# cpu3_5e2.net
KiCad netlist of a schematic drawn in EAGLE
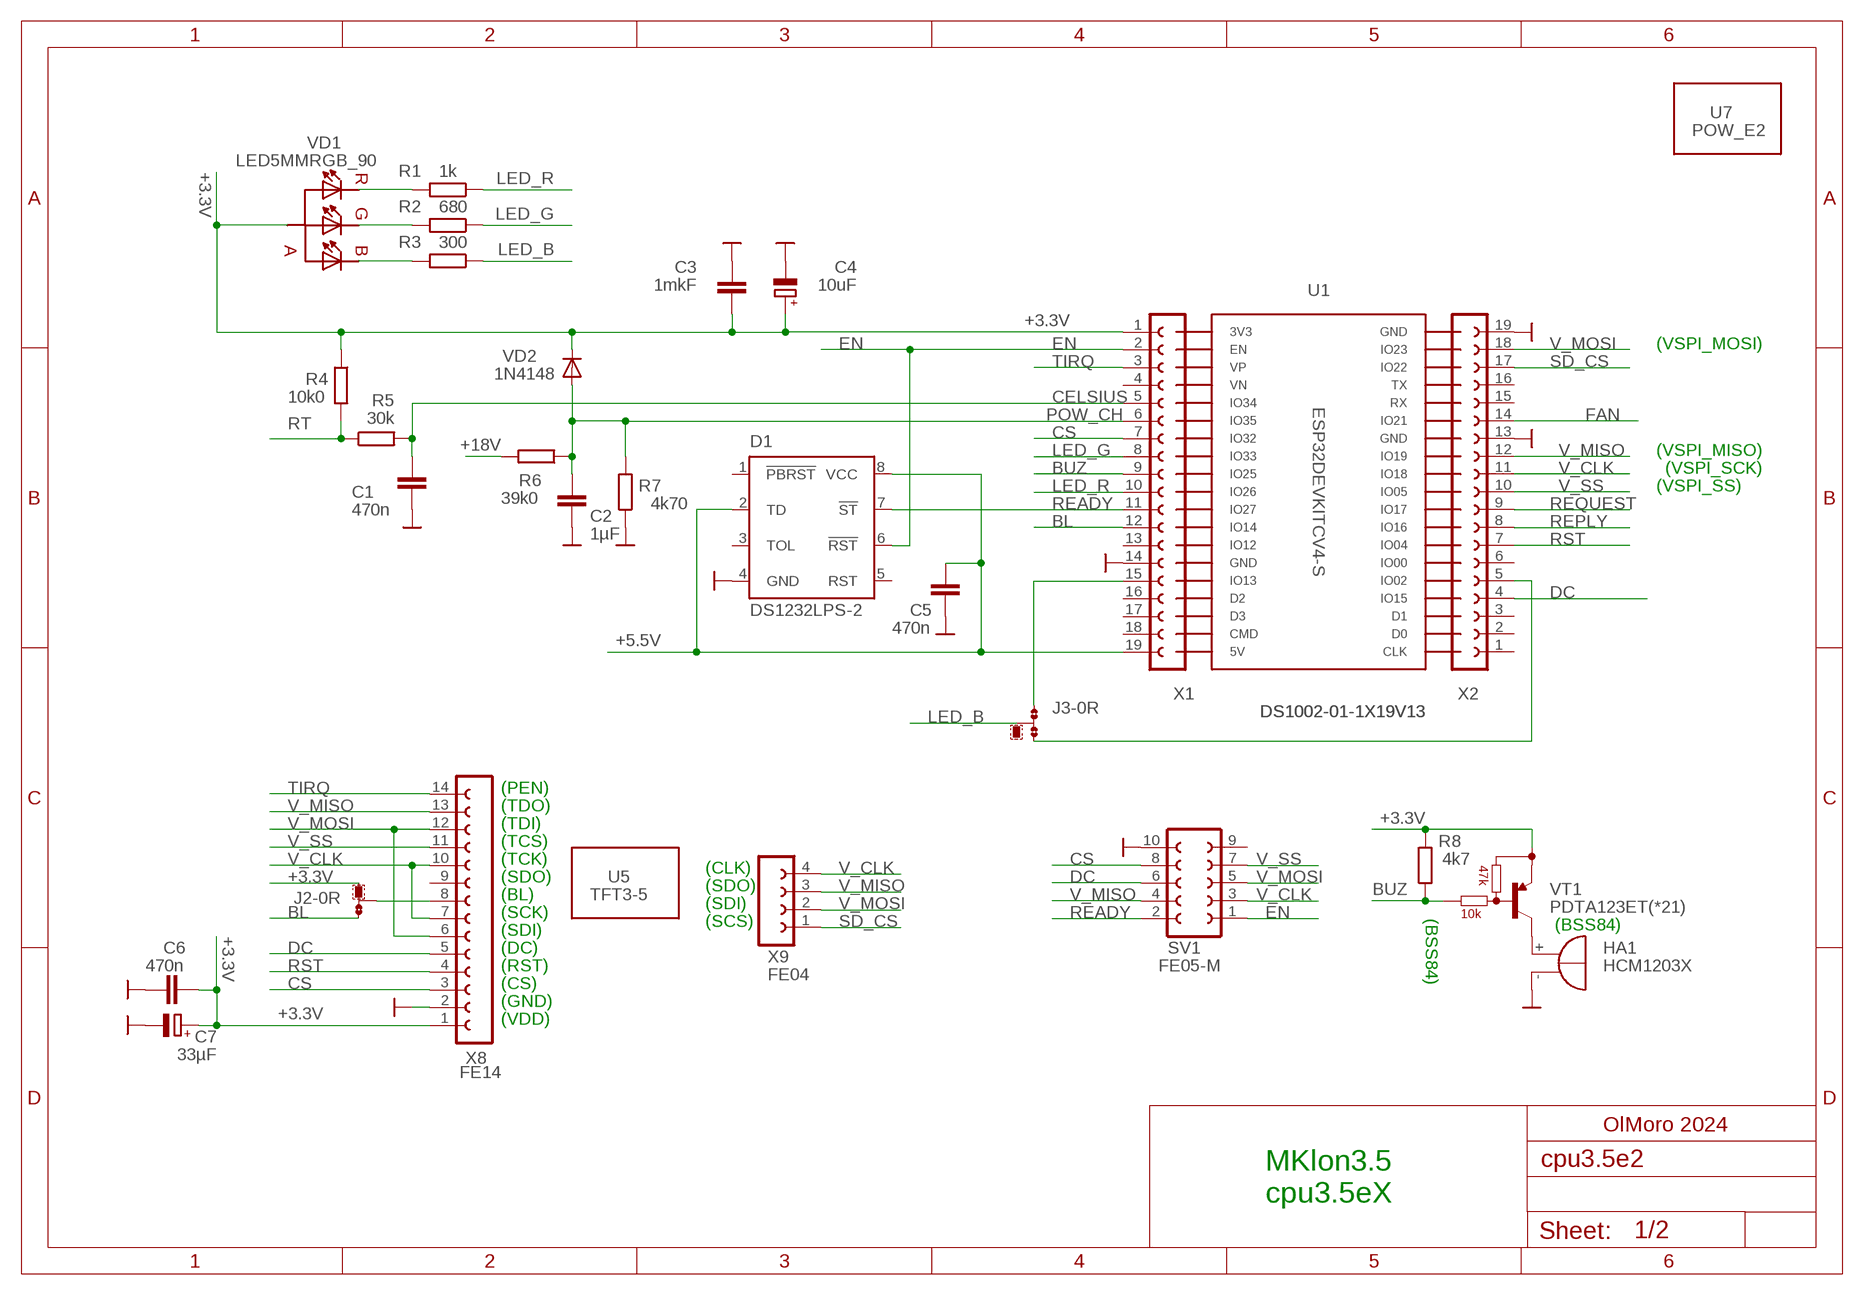
[diagram p0: schematic, sheet 1]
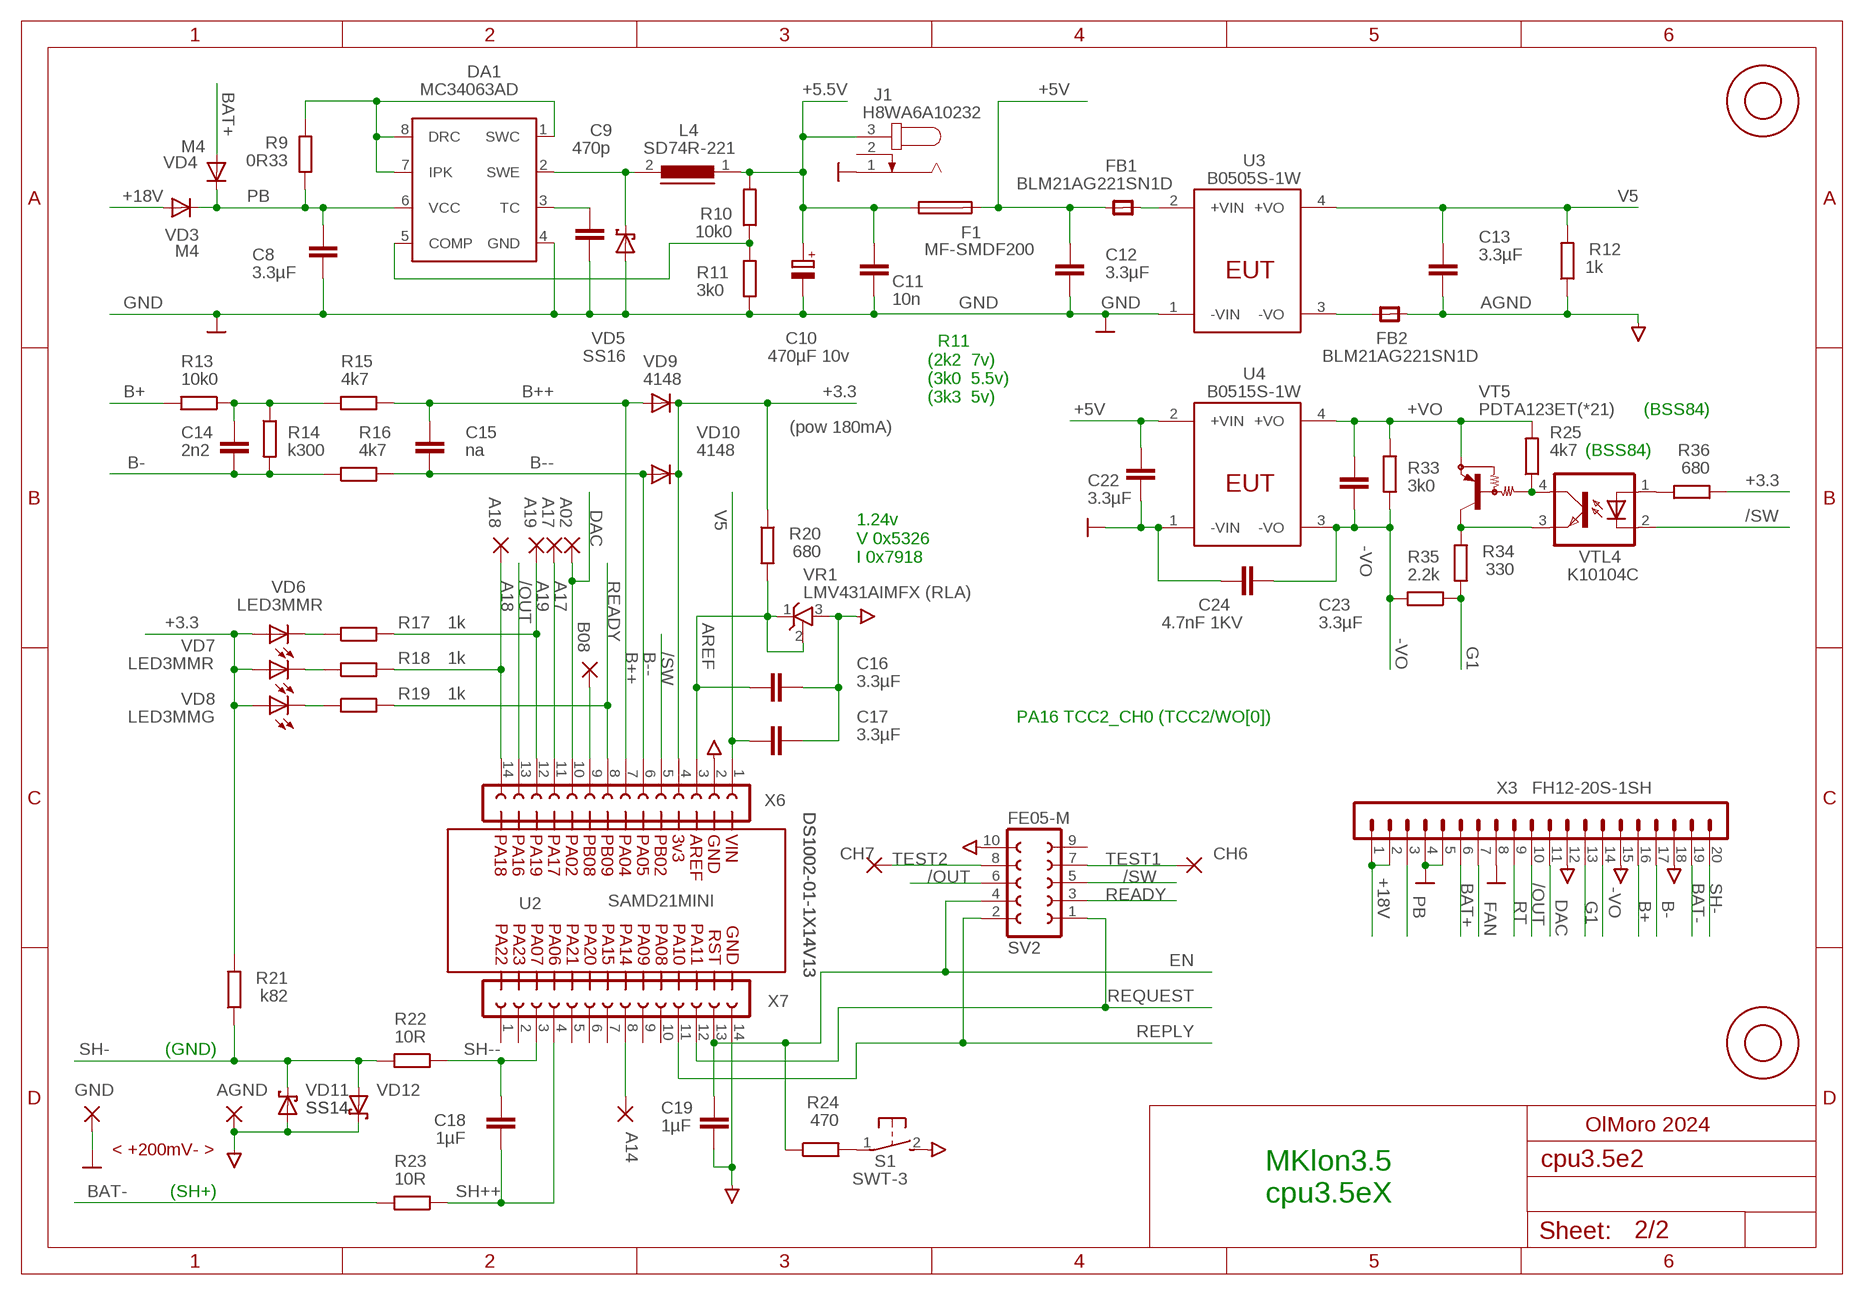
[diagram p1: schematic, sheet 2]

(export (version "E")
  (design (tool "Eeschema 10.0.6"))
  (components
    (comp (ref "A02")
      (value "WIREPAD1,6/0,8")
      (footprint "eagle-import:1,6_0,8")
      (libsource (lib "eagle-import") (part "WIREPAD1,6/0,8"))
    )
    (comp (ref "A14")
      (value "WIREPAD1,6/0,8")
      (footprint "eagle-import:1,6_0,8")
      (libsource (lib "eagle-import") (part "WIREPAD1,6/0,8"))
    )
    (comp (ref "A17")
      (value "WIREPAD1,6/0,8")
      (footprint "eagle-import:1,6_0,8")
      (libsource (lib "eagle-import") (part "WIREPAD1,6/0,8"))
    )
    (comp (ref "A18")
      (value "WIREPAD1,6/0,8")
      (footprint "eagle-import:1,6_0,8")
      (libsource (lib "eagle-import") (part "WIREPAD1,6/0,8"))
    )
    (comp (ref "A19")
      (value "WIREPAD1,6/0,8")
      (footprint "eagle-import:1,6_0,8")
      (libsource (lib "eagle-import") (part "WIREPAD1,6/0,8"))
    )
    (comp (ref "AGND")
      (value "AGND")
      (footprint "eagle-import:4,16O1,6")
      (libsource (lib "eagle-import") (part "WIREPAD4,16O1,6"))
    )
    (comp (ref "B08")
      (value "WIREPAD1,6/0,8")
      (footprint "eagle-import:1,6_0,8")
      (libsource (lib "eagle-import") (part "WIREPAD1,6/0,8"))
    )
    (comp (ref "C8")
      (value "3.3µF")
      (footprint "eagle-import:C0805")
      (libsource (lib "eagle-import") (part "C-EUC0805"))
    )
    (comp (ref "C9")
      (value "470p")
      (footprint "eagle-import:C0805")
      (libsource (lib "eagle-import") (part "C-EUC0805"))
    )
    (comp (ref "C10")
      (value "470µF 10v")
      (footprint "eagle-import:E5-8,5")
      (libsource (lib "eagle-import") (part "CPOL-EUE5-8.5"))
    )
    (comp (ref "C11")
      (value "10n")
      (footprint "eagle-import:C0805")
      (libsource (lib "eagle-import") (part "C-EUC0805"))
    )
    (comp (ref "C12")
      (value "3.3µF")
      (footprint "eagle-import:C0805")
      (libsource (lib "eagle-import") (part "C-EUC0805"))
    )
    (comp (ref "C13")
      (value "3.3µF")
      (footprint "eagle-import:C0805")
      (libsource (lib "eagle-import") (part "C-EUC0805"))
    )
    (comp (ref "C14")
      (value "2n2")
      (footprint "eagle-import:C0805")
      (libsource (lib "eagle-import") (part "C-EUC0805"))
    )
    (comp (ref "C15")
      (value "na")
      (footprint "eagle-import:C0805")
      (libsource (lib "eagle-import") (part "C-EUC0805"))
    )
    (comp (ref "C16")
      (value "3.3µF")
      (footprint "eagle-import:C0805")
      (libsource (lib "eagle-import") (part "C-EUC0805"))
    )
    (comp (ref "C17")
      (value "3.3µF")
      (footprint "eagle-import:C0805")
      (libsource (lib "eagle-import") (part "C-EUC0805"))
    )
    (comp (ref "C18")
      (value "1µF")
      (footprint "eagle-import:C0805")
      (libsource (lib "eagle-import") (part "C-EUC0805"))
    )
    (comp (ref "C19")
      (value "1µF")
      (footprint "eagle-import:C0805")
      (libsource (lib "eagle-import") (part "C-EUC0805"))
    )
    (comp (ref "C22")
      (value "3.3µF")
      (footprint "eagle-import:C0805")
      (libsource (lib "eagle-import") (part "C-EUC0805"))
    )
    (comp (ref "C23")
      (value "3.3µF")
      (footprint "eagle-import:C0805")
      (libsource (lib "eagle-import") (part "C-EUC0805"))
    )
    (comp (ref "C24")
      (value "4.7nF 1KV")
      (footprint "eagle-import:C050-024X044")
      (libsource (lib "eagle-import") (part "C-EU050-024X044"))
    )
    (comp (ref "CH6")
      (value "WIREPAD1,6/0,8")
      (footprint "eagle-import:1,6_0,8")
      (libsource (lib "eagle-import") (part "WIREPAD1,6/0,8"))
    )
    (comp (ref "CH7")
      (value "WIREPAD1,6/0,8")
      (footprint "eagle-import:1,6_0,8")
      (libsource (lib "eagle-import") (part "WIREPAD1,6/0,8"))
    )
    (comp (ref "DA1")
      (value "MC34063AD")
      (footprint "eagle-import:SO08")
      (libsource (lib "eagle-import") (part "MC34063AD"))
    )
    (comp (ref "F1")
      (value "MF-SMDF200")
      (footprint "eagle-import:MF-SMDF050")
      (libsource (lib "eagle-import") (part "MF-SMDF200"))
    )
    (comp (ref "FB1")
      (value "BLM21AG221SN1D")
      (footprint "eagle-import:0805")
      (libsource (lib "eagle-import") (part "FERRITE0805"))
    )
    (comp (ref "FB2")
      (value "BLM21AG221SN1D")
      (footprint "eagle-import:0805")
      (libsource (lib "eagle-import") (part "FERRITE0805"))
    )
    (comp (ref "GND")
      (value "GND")
      (footprint "eagle-import:4,16O1,6")
      (libsource (lib "eagle-import") (part "WIREPAD4,16O1,6"))
    )
    (comp (ref "J1")
      (value "H8WA6A10232")
      (footprint "eagle-import:SPC4077")
      (libsource (lib "eagle-import") (part "JACK-PLUG0"))
    )
    (comp (ref "L4")
      (value "SD74R-221")
      (footprint "eagle-import:DR74")
      (libsource (lib "eagle-import") (part "DR74"))
    )
    (comp (ref "R9")
      (value "0R33")
      (footprint "eagle-import:R0805")
      (libsource (lib "eagle-import") (part "R-EU_R0805"))
    )
    (comp (ref "R10")
      (value "10k0")
      (footprint "eagle-import:R0805")
      (libsource (lib "eagle-import") (part "R-EU_R0805"))
    )
    (comp (ref "R11")
      (value "3k0")
      (footprint "eagle-import:R0805")
      (libsource (lib "eagle-import") (part "R-EU_R0805"))
    )
    (comp (ref "R12")
      (value "1k")
      (footprint "eagle-import:R0805")
      (libsource (lib "eagle-import") (part "R-EU_R0805"))
    )
    (comp (ref "R13")
      (value "10k0")
      (footprint "eagle-import:R0805")
      (libsource (lib "eagle-import") (part "R-EU_R0805"))
    )
    (comp (ref "R14")
      (value "k300")
      (footprint "eagle-import:R0805")
      (libsource (lib "eagle-import") (part "R-EU_R0805"))
    )
    (comp (ref "R15")
      (value "4k7")
      (footprint "eagle-import:R0805")
      (libsource (lib "eagle-import") (part "R-EU_R0805"))
    )
    (comp (ref "R16")
      (value "4k7")
      (footprint "eagle-import:R0805")
      (libsource (lib "eagle-import") (part "R-EU_R0805"))
    )
    (comp (ref "R17")
      (value "1k")
      (footprint "eagle-import:R0805")
      (libsource (lib "eagle-import") (part "R-EU_R0805"))
    )
    (comp (ref "R18")
      (value "1k")
      (footprint "eagle-import:R0805")
      (libsource (lib "eagle-import") (part "R-EU_R0805"))
    )
    (comp (ref "R19")
      (value "1k")
      (footprint "eagle-import:R0805")
      (libsource (lib "eagle-import") (part "R-EU_R0805"))
    )
    (comp (ref "R20")
      (value "680")
      (footprint "eagle-import:R0805")
      (libsource (lib "eagle-import") (part "R-EU_R0805"))
    )
    (comp (ref "R21")
      (value "k82")
      (footprint "eagle-import:R0805")
      (libsource (lib "eagle-import") (part "R-EU_R0805"))
    )
    (comp (ref "R22")
      (value "10R")
      (footprint "eagle-import:R0805")
      (libsource (lib "eagle-import") (part "R-EU_R0805"))
    )
    (comp (ref "R23")
      (value "10R")
      (footprint "eagle-import:R0805")
      (libsource (lib "eagle-import") (part "R-EU_R0805"))
    )
    (comp (ref "R24")
      (value "470")
      (footprint "eagle-import:R0805")
      (libsource (lib "eagle-import") (part "R-EU_R0805"))
    )
    (comp (ref "R25")
      (value "4k7")
      (footprint "eagle-import:R0805")
      (libsource (lib "eagle-import") (part "R-EU_R0805"))
    )
    (comp (ref "R33")
      (value "3k0")
      (footprint "eagle-import:R0805")
      (libsource (lib "eagle-import") (part "R-EU_R0805"))
    )
    (comp (ref "R34")
      (value "330")
      (footprint "eagle-import:R0805")
      (libsource (lib "eagle-import") (part "R-EU_R0805"))
    )
    (comp (ref "R35")
      (value "2.2k")
      (footprint "eagle-import:R0805")
      (libsource (lib "eagle-import") (part "R-EU_R0805"))
    )
    (comp (ref "R36")
      (value "680")
      (footprint "eagle-import:R0805")
      (libsource (lib "eagle-import") (part "R-EU_R0805"))
    )
    (comp (ref "S1")
      (value "SWT-3")
      (footprint "eagle-import:B3F-31XX")
      (fields (field (name "MPN") "B3F-3100"))
      (libsource (lib "eagle-import") (part "31-XX"))
    )
    (comp (ref "SV2")
      (value "FE05-M")
      (footprint "eagle-import:FE05-2M")
      (libsource (lib "eagle-import") (part "FE05-M"))
    )
    (comp (ref "U$6")
      (value "M3X20")
      (footprint "eagle-import:M3X20")
      (libsource (lib "eagle-import") (part "M3X20"))
    )
    (comp (ref "U$15")
      (value "M3X20")
      (footprint "eagle-import:M3X20")
      (libsource (lib "eagle-import") (part "M3X20"))
    )
    (comp (ref "U$16")
      (value "M3X20")
      (footprint "eagle-import:M3X20")
      (libsource (lib "eagle-import") (part "M3X20"))
    )
    (comp (ref "U$18")
      (value "M3X20")
      (footprint "eagle-import:M3X20")
      (libsource (lib "eagle-import") (part "M3X20"))
    )
    (comp (ref "U$19")
      (value "M3X12")
      (footprint "eagle-import:M3X12")
      (libsource (lib "eagle-import") (part "M3X12"))
    )
    (comp (ref "U$21")
      (value "M3X12")
      (footprint "eagle-import:M3X12")
      (libsource (lib "eagle-import") (part "M3X12"))
    )
    (comp (ref "U$23")
      (value "M3X12")
      (footprint "eagle-import:M3X12")
      (libsource (lib "eagle-import") (part "M3X12"))
    )
    (comp (ref "U$27")
      (value "M3X12")
      (footprint "eagle-import:M3X12")
      (libsource (lib "eagle-import") (part "M3X12"))
    )
    (comp (ref "U2")
      (value "SAMD21MINI")
      (footprint "eagle-import:SAMD21MINI")
      (libsource (lib "eagle-import") (part "SAMD21MINI"))
    )
    (comp (ref "U3")
      (value "B0505S-1W")
      (footprint "eagle-import:HLK-1D1212")
      (libsource (lib "eagle-import") (part "HLK-1D1212"))
    )
    (comp (ref "U4")
      (value "B0515S-1W")
      (footprint "eagle-import:HLK-1D1212")
      (libsource (lib "eagle-import") (part "HLK-1D1212"))
    )
    (comp (ref "VD3")
      (value "M4")
      (footprint "eagle-import:DO214AC")
      (libsource (lib "eagle-import") (part "DIODE-DO214AC"))
    )
    (comp (ref "VD4")
      (value "M4")
      (footprint "eagle-import:DO214AC")
      (libsource (lib "eagle-import") (part "DIODE-DO214AC"))
    )
    (comp (ref "VD5")
      (value "SS16")
      (footprint "eagle-import:DO214AC")
      (libsource (lib "eagle-import") (part "SS16"))
    )
    (comp (ref "VD6")
      (value "LED3MMR")
      (footprint "eagle-import:LED3MMR")
      (libsource (lib "eagle-import") (part "LED3MMR"))
    )
    (comp (ref "VD7")
      (value "LED3MMR")
      (footprint "eagle-import:LED3MMR")
      (libsource (lib "eagle-import") (part "LED3MMR"))
    )
    (comp (ref "VD8")
      (value "LED3MMG")
      (footprint "eagle-import:LED3MMG")
      (libsource (lib "eagle-import") (part "LED3MMG"))
    )
    (comp (ref "VD9")
      (value "4148")
      (footprint "eagle-import:MINIMELF")
      (libsource (lib "eagle-import") (part "DIODE-MINIMELF"))
    )
    (comp (ref "VD10")
      (value "4148")
      (footprint "eagle-import:MINIMELF")
      (libsource (lib "eagle-import") (part "DIODE-MINIMELF"))
    )
    (comp (ref "VD11")
      (value "SS14")
      (footprint "eagle-import:DO214AC")
      (libsource (lib "eagle-import") (part "SS16"))
    )
    (comp (ref "VD12")
      (value "SS14")
      (footprint "eagle-import:DO214AC")
      (libsource (lib "eagle-import") (part "SS16"))
    )
    (comp (ref "VR1")
      (value "LMV431AIMFX (RLA)")
      (footprint "eagle-import:SOT23")
      (libsource (lib "eagle-import") (part "TL431-SOT23-3"))
    )
    (comp (ref "VT5")
      (value "PDTA123ET(*21)")
      (footprint "eagle-import:SC59-BEC")
      (libsource (lib "eagle-import") (part "MUN2113T1"))
    )
    (comp (ref "VTL4")
      (value "K10104C")
      (footprint "eagle-import:SMD4-7")
      (libsource (lib "eagle-import") (part "SFH618?A-3X007"))
    )
    (comp (ref "X3")
      (value "FH12-20S-1SH")
      (footprint "eagle-import:FH12-20S-1SH")
      (libsource (lib "eagle-import") (part "FH12-20S-1SH"))
    )
    (comp (ref "X6")
      (value "DS1002-01-1X14V13")
      (footprint "eagle-import:DS1002-01-1X14V13")
      (libsource (lib "eagle-import") (part "DS1002-01-1X14V13"))
    )
    (comp (ref "X7")
      (value "DS1002-01-1X14V13")
      (footprint "eagle-import:DS1002-01-1X14V13")
      (libsource (lib "eagle-import") (part "DS1002-01-1X14V13"))
    )
    (comp (ref "C1")
      (value "470n")
      (footprint "eagle-import:C0805")
      (libsource (lib "eagle-import") (part "C-EUC0805"))
    )
    (comp (ref "C2")
      (value "1µF")
      (footprint "eagle-import:C0805")
      (libsource (lib "eagle-import") (part "C-EUC0805"))
    )
    (comp (ref "C3")
      (value "1mkF")
      (footprint "eagle-import:C0805")
      (libsource (lib "eagle-import") (part "C-EUC0805"))
    )
    (comp (ref "C4")
      (value "10uF")
      (footprint "eagle-import:CT3528")
      (libsource (lib "eagle-import") (part "CPOL-EUCT3528"))
    )
    (comp (ref "C5")
      (value "470n")
      (footprint "eagle-import:C0805")
      (libsource (lib "eagle-import") (part "C-EUC0805"))
    )
    (comp (ref "C6")
      (value "470n")
      (footprint "eagle-import:C0805")
      (libsource (lib "eagle-import") (part "C-EUC0805"))
    )
    (comp (ref "C7")
      (value "33µF")
      (footprint "eagle-import:CT6032")
      (libsource (lib "eagle-import") (part "CPOL-EUCT6032"))
    )
    (comp (ref "D1")
      (value "DS1232LPS-2")
      (footprint "eagle-import:SO-08")
      (fields (field (name "MF") "DALLAS SEMICONDUCTOR"))
      (libsource (lib "eagle-import") (part "DS1232LPS-2"))
    )
    (comp (ref "HA1")
      (value "HCM1203X")
      (footprint "eagle-import:BMT1205XH7.5")
      (libsource (lib "eagle-import") (part "BMT1205XH7.5"))
    )
    (comp (ref "J2")
      (value "0R-JUMPB")
      (footprint "eagle-import:B0R-JMP")
      (libsource (lib "eagle-import") (part "0R-JUMPB"))
    )
    (comp (ref "J3")
      (value "0R-JUMPB")
      (footprint "eagle-import:B0R-JMP")
      (libsource (lib "eagle-import") (part "0R-JUMPB"))
    )
    (comp (ref "R1")
      (value "1k")
      (footprint "eagle-import:R0805")
      (libsource (lib "eagle-import") (part "R-EU_R0805"))
    )
    (comp (ref "R2")
      (value "680")
      (footprint "eagle-import:R0805")
      (libsource (lib "eagle-import") (part "R-EU_R0805"))
    )
    (comp (ref "R3")
      (value "300")
      (footprint "eagle-import:R0805")
      (libsource (lib "eagle-import") (part "R-EU_R0805"))
    )
    (comp (ref "R4")
      (value "10k0")
      (footprint "eagle-import:R0805")
      (libsource (lib "eagle-import") (part "R-EU_R0805"))
    )
    (comp (ref "R5")
      (value "30k")
      (footprint "eagle-import:R0805")
      (libsource (lib "eagle-import") (part "R-EU_R0805"))
    )
    (comp (ref "R6")
      (value "39k0")
      (footprint "eagle-import:R0805")
      (libsource (lib "eagle-import") (part "R-EU_R0805"))
    )
    (comp (ref "R7")
      (value "4k70")
      (footprint "eagle-import:R0805")
      (libsource (lib "eagle-import") (part "R-EU_R0805"))
    )
    (comp (ref "R8")
      (value "4k7")
      (footprint "eagle-import:R0805")
      (libsource (lib "eagle-import") (part "R-EU_R0805"))
    )
    (comp (ref "SV1")
      (value "FE05-M")
      (footprint "eagle-import:FE05-2M")
      (libsource (lib "eagle-import") (part "FE05-M"))
    )
    (comp (ref "U1")
      (value "ESP32DEVKITCV4-S")
      (footprint "eagle-import:ESP32DEVKITCV4-S")
      (libsource (lib "eagle-import") (part "ESP32DEVKITCV4-S"))
    )
    (comp (ref "U5")
      (value "TFT3-5")
      (footprint "eagle-import:TFT3-5")
      (libsource (lib "eagle-import") (part "TFT3-5"))
    )
    (comp (ref "U7")
      (value "POW_E2")
      (footprint "eagle-import:POW3_5")
      (libsource (lib "eagle-import") (part "POW3_5"))
    )
    (comp (ref "VD1")
      (value "LED5MMRGB_90")
      (footprint "eagle-import:LED5MMRGB_90")
      (libsource (lib "eagle-import") (part "LED5MMRGB_90"))
    )
    (comp (ref "VD2")
      (value "1N4148")
      (footprint "eagle-import:MINIMELF")
      (libsource (lib "eagle-import") (part "DIODE-MINIMELF"))
    )
    (comp (ref "VT1")
      (value "PDTA123ET(*21)")
      (footprint "eagle-import:SOT23-BEC")
      (libsource (lib "eagle-import") (part "BCR185"))
    )
    (comp (ref "X1")
      (value "DS1002-01-1X19V13")
      (footprint "eagle-import:DS1002-01-1X19V13")
      (libsource (lib "eagle-import") (part "DS1002-01-1X19V13"))
    )
    (comp (ref "X2")
      (value "DS1002-01-1X19V13")
      (footprint "eagle-import:DS1002-01-1X19V13")
      (libsource (lib "eagle-import") (part "DS1002-01-1X19V13"))
    )
    (comp (ref "X8")
      (value "FE14")
      (footprint "eagle-import:FE14")
      (libsource (lib "eagle-import") (part "FE14"))
    )
    (comp (ref "X9")
      (value "FE04")
      (footprint "eagle-import:FE04")
      (libsource (lib "eagle-import") (part "FE04"))
    )
  )
  (nets
    (net (code "1") (name "+3.3") (class "Default")
      (node (ref "R20") (pin "1") (pinfunction "1_1") (pintype "passive"))
      (node (ref "R21") (pin "2") (pinfunction "2_2") (pintype "passive"))
      (node (ref "R36") (pin "1") (pinfunction "1_1") (pintype "passive"))
      (node (ref "VD10") (pin "C") (pinfunction "C_C") (pintype "passive"))
      (node (ref "VD6") (pin "A") (pinfunction "A_A") (pintype "passive"))
      (node (ref "VD7") (pin "A") (pinfunction "A_A") (pintype "passive"))
      (node (ref "VD8") (pin "A") (pinfunction "A_A") (pintype "passive"))
      (node (ref "VD9") (pin "C") (pinfunction "C_C") (pintype "passive"))
      (node (ref "X6") (pin "4") (pinfunction "4_4") (pintype "passive"))
    )
    (net (code "2") (name "+3.3V") (class "Default")
      (node (ref "C3") (pin "1") (pinfunction "1_1") (pintype "passive"))
      (node (ref "C4") (pin "+") (pinfunction "+_+") (pintype "passive"))
      (node (ref "C6") (pin "1") (pinfunction "1_1") (pintype "passive"))
      (node (ref "C7") (pin "+") (pinfunction "+_+") (pintype "passive"))
      (node (ref "J2") (pin "1") (pinfunction "1_1") (pintype "passive"))
      (node (ref "R4") (pin "1") (pinfunction "1_1") (pintype "passive"))
      (node (ref "R8") (pin "2") (pinfunction "2_2") (pintype "passive"))
      (node (ref "VD1") (pin "P$3") (pinfunction "A_P$3") (pintype "bidirectional"))
      (node (ref "VD2") (pin "C") (pinfunction "C_C") (pintype "passive"))
      (node (ref "VT1") (pin "E") (pinfunction "E_E") (pintype "passive"))
      (node (ref "X1") (pin "1") (pinfunction "1_1") (pintype "passive"))
      (node (ref "X8") (pin "1") (pinfunction "1_1") (pintype "passive"))
    )
    (net (code "3") (name "+5.5V") (class "Default")
      (node (ref "C10") (pin "+") (pinfunction "+_+") (pintype "passive"))
      (node (ref "C11") (pin "1") (pinfunction "1_1") (pintype "passive"))
      (node (ref "C5") (pin "1") (pinfunction "1_1") (pintype "passive"))
      (node (ref "D1") (pin "2") (pinfunction "TD_2") (pintype "input"))
      (node (ref "D1") (pin "8") (pinfunction "VCC_8") (pintype "power_in"))
      (node (ref "F1") (pin "1") (pinfunction "1_1") (pintype "passive"))
      (node (ref "J1") (pin "3") (pinfunction "3_3") (pintype "passive"))
      (node (ref "L4") (pin "1") (pinfunction "1_1") (pintype "passive"))
      (node (ref "R10") (pin "2") (pinfunction "2_2") (pintype "passive"))
      (node (ref "X1") (pin "19") (pinfunction "19_19") (pintype "passive"))
    )
    (net (code "4") (name "+5V") (class "Default")
      (node (ref "C12") (pin "1") (pinfunction "1_1") (pintype "passive"))
      (node (ref "C22") (pin "2") (pinfunction "2_2") (pintype "passive"))
      (node (ref "F1") (pin "2") (pinfunction "2_2") (pintype "passive"))
      (node (ref "FB1") (pin "1") (pinfunction "P$1_1") (pintype "passive"))
      (node (ref "U4") (pin "2") (pinfunction "+VIN_2") (pintype "power_in"))
    )
    (net (code "5") (name "+18V") (class "Default")
      (node (ref "R6") (pin "2") (pinfunction "2_2") (pintype "passive"))
      (node (ref "VD3") (pin "A") (pinfunction "A_A") (pintype "passive"))
      (node (ref "X3") (pin "1") (pinfunction "1_1") (pintype "passive"))
      (node (ref "X3") (pin "2") (pinfunction "2_2") (pintype "passive"))
    )
    (net (code "6") (name "+VO") (class "Default")
      (node (ref "C23") (pin "2") (pinfunction "2_2") (pintype "passive"))
      (node (ref "R25") (pin "2") (pinfunction "2_2") (pintype "passive"))
      (node (ref "R33") (pin "2") (pinfunction "2_2") (pintype "passive"))
      (node (ref "U4") (pin "4") (pinfunction "+VO_4") (pintype "power_in"))
      (node (ref "VT5") (pin "E") (pinfunction "E_E") (pintype "passive"))
    )
    (net (code "7") (name "-VO") (class "Default")
      (node (ref "C23") (pin "1") (pinfunction "1_1") (pintype "passive"))
      (node (ref "C24") (pin "2") (pinfunction "2_2") (pintype "passive"))
      (node (ref "R33") (pin "1") (pinfunction "1_1") (pintype "passive"))
      (node (ref "R35") (pin "2") (pinfunction "2_2") (pintype "passive"))
      (node (ref "U4") (pin "3") (pinfunction "-VO_3") (pintype "power_in"))
      (node (ref "X3") (pin "14") (pinfunction "14_14") (pintype "passive"))
    )
    (net (code "8") (name "A17") (class "Default")
      (node (ref "A17") (pin "1") (pinfunction "P_1") (pintype "passive"))
      (node (ref "X6") (pin "11") (pinfunction "11_11") (pintype "passive"))
    )
    (net (code "9") (name "A18") (class "Default")
      (node (ref "A18") (pin "1") (pinfunction "P_1") (pintype "passive"))
      (node (ref "R18") (pin "2") (pinfunction "2_2") (pintype "passive"))
      (node (ref "X6") (pin "14") (pinfunction "14_14") (pintype "passive"))
    )
    (net (code "10") (name "A19") (class "Default")
      (node (ref "A19") (pin "1") (pinfunction "P_1") (pintype "passive"))
      (node (ref "R17") (pin "2") (pinfunction "2_2") (pintype "passive"))
      (node (ref "X6") (pin "12") (pinfunction "12_12") (pintype "passive"))
    )
    (net (code "11") (name "AGND") (class "Default")
      (node (ref "AGND") (pin "1") (pinfunction "P_1") (pintype "passive"))
      (node (ref "C13") (pin "2") (pinfunction "2_2") (pintype "passive"))
      (node (ref "C16") (pin "2") (pinfunction "2_2") (pintype "passive"))
      (node (ref "C17") (pin "2") (pinfunction "2_2") (pintype "passive"))
      (node (ref "C19") (pin "2") (pinfunction "2_2") (pintype "passive"))
      (node (ref "FB2") (pin "2") (pinfunction "P$2_2") (pintype "passive"))
      (node (ref "R12") (pin "1") (pinfunction "1_1") (pintype "passive"))
      (node (ref "S1") (pin "2") (pinfunction "S_2") (pintype "passive"))
      (node (ref "SV2") (pin "10") (pinfunction "10_10") (pintype "passive"))
      (node (ref "VD11") (pin "A") (pinfunction "A_A") (pintype "passive"))
      (node (ref "VD12") (pin "C") (pinfunction "C_C") (pintype "passive"))
      (node (ref "VR1") (pin "3") (pinfunction "A_3") (pintype "passive"))
      (node (ref "X3") (pin "12") (pinfunction "12_12") (pintype "passive"))
      (node (ref "X3") (pin "15") (pinfunction "15_15") (pintype "passive"))
      (node (ref "X3") (pin "18") (pinfunction "18_18") (pintype "passive"))
      (node (ref "X6") (pin "2") (pinfunction "2_2") (pintype "passive"))
      (node (ref "X7") (pin "14") (pinfunction "14_14") (pintype "passive"))
    )
    (net (code "12") (name "AREF") (class "Default")
      (node (ref "C16") (pin "1") (pinfunction "1_1") (pintype "passive"))
      (node (ref "R20") (pin "2") (pinfunction "2_2") (pintype "passive"))
      (node (ref "VR1") (pin "1") (pinfunction "C_1") (pintype "passive"))
      (node (ref "VR1") (pin "2") (pinfunction "R_2") (pintype "passive"))
      (node (ref "X6") (pin "3") (pinfunction "3_3") (pintype "passive"))
    )
    (net (code "13") (name "B+") (class "Default")
      (node (ref "R13") (pin "2") (pinfunction "2_2") (pintype "passive"))
      (node (ref "X3") (pin "16") (pinfunction "16_16") (pintype "passive"))
    )
    (net (code "14") (name "B++") (class "Default")
      (node (ref "C15") (pin "1") (pinfunction "1_1") (pintype "passive"))
      (node (ref "R15") (pin "2") (pinfunction "2_2") (pintype "passive"))
      (node (ref "VD9") (pin "A") (pinfunction "A_A") (pintype "passive"))
      (node (ref "X6") (pin "7") (pinfunction "7_7") (pintype "passive"))
    )
    (net (code "15") (name "B-") (class "Default")
      (node (ref "C14") (pin "2") (pinfunction "2_2") (pintype "passive"))
      (node (ref "R14") (pin "2") (pinfunction "2_2") (pintype "passive"))
      (node (ref "R16") (pin "1") (pinfunction "1_1") (pintype "passive"))
      (node (ref "X3") (pin "17") (pinfunction "17_17") (pintype "passive"))
    )
    (net (code "16") (name "B--") (class "Default")
      (node (ref "C15") (pin "2") (pinfunction "2_2") (pintype "passive"))
      (node (ref "R16") (pin "2") (pinfunction "2_2") (pintype "passive"))
      (node (ref "VD10") (pin "A") (pinfunction "A_A") (pintype "passive"))
      (node (ref "X6") (pin "6") (pinfunction "6_6") (pintype "passive"))
    )
    (net (code "17") (name "BAT+") (class "Default")
      (node (ref "VD4") (pin "A") (pinfunction "A_A") (pintype "passive"))
      (node (ref "X3") (pin "6") (pinfunction "6_6") (pintype "passive"))
    )
    (net (code "18") (name "BAT-") (class "Default")
      (node (ref "R23") (pin "2") (pinfunction "2_2") (pintype "passive"))
      (node (ref "X3") (pin "19") (pinfunction "19_19") (pintype "passive"))
    )
    (net (code "19") (name "BL") (class "Default")
      (node (ref "J2") (pin "3") (pinfunction "3_3") (pintype "passive"))
      (node (ref "X1") (pin "12") (pinfunction "12_12") (pintype "passive"))
    )
    (net (code "20") (name "BUZ") (class "Default")
      (node (ref "R8") (pin "1") (pinfunction "1_1") (pintype "passive"))
      (node (ref "VT1") (pin "B") (pinfunction "B_B") (pintype "passive"))
      (node (ref "X1") (pin "9") (pinfunction "9_9") (pintype "passive"))
    )
    (net (code "21") (name "CELSIUS") (class "Default")
      (node (ref "C1") (pin "1") (pinfunction "1_1") (pintype "passive"))
      (node (ref "R5") (pin "2") (pinfunction "2_2") (pintype "passive"))
      (node (ref "X1") (pin "5") (pinfunction "5_5") (pintype "passive"))
    )
    (net (code "22") (name "CS") (class "Default")
      (node (ref "SV1") (pin "8") (pinfunction "8_8") (pintype "passive"))
      (node (ref "X1") (pin "7") (pinfunction "7_7") (pintype "passive"))
      (node (ref "X8") (pin "3") (pinfunction "3_3") (pintype "passive"))
    )
    (net (code "23") (name "DAC") (class "Default")
      (node (ref "A02") (pin "1") (pinfunction "P_1") (pintype "passive"))
      (node (ref "X3") (pin "11") (pinfunction "11_11") (pintype "passive"))
      (node (ref "X6") (pin "10") (pinfunction "10_10") (pintype "passive"))
    )
    (net (code "24") (name "DC") (class "Default")
      (node (ref "SV1") (pin "6") (pinfunction "6_6") (pintype "passive"))
      (node (ref "X2") (pin "4") (pinfunction "4_4") (pintype "passive"))
      (node (ref "X8") (pin "5") (pinfunction "5_5") (pintype "passive"))
    )
    (net (code "25") (name "EN") (class "Default")
      (node (ref "C19") (pin "1") (pinfunction "1_1") (pintype "passive"))
      (node (ref "D1") (pin "6") (pinfunction "~{RST}_6") (pintype "output"))
      (node (ref "R24") (pin "1") (pinfunction "1_1") (pintype "passive"))
      (node (ref "SV1") (pin "1") (pinfunction "1_1") (pintype "passive"))
      (node (ref "SV2") (pin "4") (pinfunction "4_4") (pintype "passive"))
      (node (ref "X1") (pin "2") (pinfunction "2_2") (pintype "passive"))
      (node (ref "X7") (pin "13") (pinfunction "13_13") (pintype "passive"))
    )
    (net (code "26") (name "FAN") (class "Default")
      (node (ref "X2") (pin "14") (pinfunction "14_14") (pintype "passive"))
      (node (ref "X3") (pin "7") (pinfunction "7_7") (pintype "passive"))
    )
    (net (code "27") (name "G1") (class "Default")
      (node (ref "R34") (pin "1") (pinfunction "1_1") (pintype "passive"))
      (node (ref "R35") (pin "1") (pinfunction "1_1") (pintype "passive"))
      (node (ref "X3") (pin "13") (pinfunction "13_13") (pintype "passive"))
    )
    (net (code "28") (name "GND") (class "Default")
      (node (ref "C1") (pin "2") (pinfunction "2_2") (pintype "passive"))
      (node (ref "C10") (pin "-") (pinfunction "-_-") (pintype "passive"))
      (node (ref "C11") (pin "2") (pinfunction "2_2") (pintype "passive"))
      (node (ref "C12") (pin "2") (pinfunction "2_2") (pintype "passive"))
      (node (ref "C2") (pin "2") (pinfunction "2_2") (pintype "passive"))
      (node (ref "C22") (pin "1") (pinfunction "1_1") (pintype "passive"))
      (node (ref "C24") (pin "1") (pinfunction "1_1") (pintype "passive"))
      (node (ref "C3") (pin "2") (pinfunction "2_2") (pintype "passive"))
      (node (ref "C4") (pin "-") (pinfunction "-_-") (pintype "passive"))
      (node (ref "C5") (pin "2") (pinfunction "2_2") (pintype "passive"))
      (node (ref "C6") (pin "2") (pinfunction "2_2") (pintype "passive"))
      (node (ref "C7") (pin "-") (pinfunction "-_-") (pintype "passive"))
      (node (ref "C8") (pin "2") (pinfunction "2_2") (pintype "passive"))
      (node (ref "C9") (pin "2") (pinfunction "2_2") (pintype "passive"))
      (node (ref "D1") (pin "4") (pinfunction "GND_4") (pintype "power_in"))
      (node (ref "DA1") (pin "4") (pinfunction "GND_4") (pintype "power_in"))
      (node (ref "GND") (pin "1") (pinfunction "P_1") (pintype "passive"))
      (node (ref "HA1") (pin "-") (pinfunction "-_-") (pintype "passive"))
      (node (ref "J1") (pin "1") (pinfunction "1_1") (pintype "passive"))
      (node (ref "R11") (pin "1") (pinfunction "1_1") (pintype "passive"))
      (node (ref "R7") (pin "1") (pinfunction "1_1") (pintype "passive"))
      (node (ref "SV1") (pin "10") (pinfunction "10_10") (pintype "passive"))
      (node (ref "U3") (pin "1") (pinfunction "-VIN_1") (pintype "power_in"))
      (node (ref "U4") (pin "1") (pinfunction "-VIN_1") (pintype "power_in"))
      (node (ref "VD5") (pin "A") (pinfunction "A_A") (pintype "passive"))
      (node (ref "X1") (pin "14") (pinfunction "14_14") (pintype "passive"))
      (node (ref "X2") (pin "13") (pinfunction "13_13") (pintype "passive"))
      (node (ref "X2") (pin "19") (pinfunction "19_19") (pintype "passive"))
      (node (ref "X3") (pin "4") (pinfunction "4_4") (pintype "passive"))
      (node (ref "X3") (pin "5") (pinfunction "5_5") (pintype "passive"))
      (node (ref "X3") (pin "8") (pinfunction "8_8") (pintype "passive"))
      (node (ref "X8") (pin "2") (pinfunction "2_2") (pintype "passive"))
    )
    (net (code "29") (name "LED_B") (class "Default")
      (node (ref "J3") (pin "2") (pinfunction "2_2") (pintype "passive"))
      (node (ref "J3") (pin "3") (pinfunction "3_3") (pintype "passive"))
      (node (ref "R3") (pin "1") (pinfunction "1_1") (pintype "passive"))
      (node (ref "X1") (pin "15") (pinfunction "15_15") (pintype "passive"))
    )
    (net (code "30") (name "LED_G") (class "Default")
      (node (ref "R2") (pin "1") (pinfunction "1_1") (pintype "passive"))
      (node (ref "X1") (pin "8") (pinfunction "8_8") (pintype "passive"))
    )
    (net (code "31") (name "LED_R") (class "Default")
      (node (ref "R1") (pin "1") (pinfunction "1_1") (pintype "passive"))
      (node (ref "X1") (pin "10") (pinfunction "10_10") (pintype "passive"))
    )
    (net (code "32") (name "Net-(A14-P)") (class "Default")
      (node (ref "A14") (pin "1") (pinfunction "P_1") (pintype "passive"))
      (node (ref "X7") (pin "8") (pinfunction "8_8") (pintype "passive"))
    )
    (net (code "33") (name "Net-(B08-P)") (class "Default")
      (node (ref "B08") (pin "1") (pinfunction "P_1") (pintype "passive"))
      (node (ref "X6") (pin "9") (pinfunction "9_9") (pintype "passive"))
    )
    (net (code "34") (name "Net-(C14-Pad1)") (class "Default")
      (node (ref "C14") (pin "1") (pinfunction "1_1") (pintype "passive"))
      (node (ref "R13") (pin "1") (pinfunction "1_1") (pintype "passive"))
      (node (ref "R14") (pin "1") (pinfunction "1_1") (pintype "passive"))
      (node (ref "R15") (pin "1") (pinfunction "1_1") (pintype "passive"))
    )
    (net (code "35") (name "Net-(DA1-COMP)") (class "Default")
      (node (ref "DA1") (pin "5") (pinfunction "COMP_5") (pintype "input"))
      (node (ref "R10") (pin "1") (pinfunction "1_1") (pintype "passive"))
      (node (ref "R11") (pin "2") (pinfunction "2_2") (pintype "passive"))
    )
    (net (code "36") (name "Net-(DA1-DRC)") (class "Default")
      (node (ref "DA1") (pin "1") (pinfunction "SWC_1") (pintype "bidirectional"))
      (node (ref "DA1") (pin "7") (pinfunction "IPK_7") (pintype "input"))
      (node (ref "DA1") (pin "8") (pinfunction "DRC_8") (pintype "input"))
      (node (ref "R9") (pin "2") (pinfunction "2_2") (pintype "passive"))
    )
    (net (code "37") (name "Net-(DA1-SWE)") (class "Default")
      (node (ref "DA1") (pin "2") (pinfunction "SWE_2") (pintype "bidirectional"))
      (node (ref "L4") (pin "2") (pinfunction "2_2") (pintype "passive"))
      (node (ref "VD5") (pin "C") (pinfunction "C_C") (pintype "passive"))
    )
    (net (code "38") (name "Net-(DA1-TC)") (class "Default")
      (node (ref "C9") (pin "1") (pinfunction "1_1") (pintype "passive"))
      (node (ref "DA1") (pin "3") (pinfunction "TC_3") (pintype "passive"))
    )
    (net (code "39") (name "Net-(FB1-P$2)") (class "Default")
      (node (ref "FB1") (pin "2") (pinfunction "P$2_2") (pintype "passive"))
      (node (ref "U3") (pin "2") (pinfunction "+VIN_2") (pintype "power_in"))
    )
    (net (code "40") (name "Net-(FB2-P$1)") (class "Default")
      (node (ref "FB2") (pin "1") (pinfunction "P$1_1") (pintype "passive"))
      (node (ref "U3") (pin "3") (pinfunction "-VO_3") (pintype "power_in"))
    )
    (net (code "41") (name "Net-(HA1-Pad+)") (class "Default")
      (node (ref "HA1") (pin "+") (pinfunction "+_+") (pintype "passive"))
      (node (ref "VT1") (pin "C") (pinfunction "C_C") (pintype "passive"))
    )
    (net (code "42") (name "Net-(J2-Pad2)") (class "Default")
      (node (ref "J2") (pin "2") (pinfunction "2_2") (pintype "passive"))
      (node (ref "X8") (pin "8") (pinfunction "8_8") (pintype "passive"))
    )
    (net (code "43") (name "Net-(J3-Pad1)") (class "Default")
      (node (ref "J3") (pin "1") (pinfunction "1_1") (pintype "passive"))
      (node (ref "X2") (pin "5") (pinfunction "5_5") (pintype "passive"))
    )
    (net (code "44") (name "Net-(S1-P)") (class "Default")
      (node (ref "R24") (pin "2") (pinfunction "2_2") (pintype "passive"))
      (node (ref "S1") (pin "1") (pinfunction "P_1") (pintype "passive"))
    )
    (net (code "45") (name "Net-(VD1-BLUE)") (class "Default")
      (node (ref "R3") (pin "2") (pinfunction "2_2") (pintype "passive"))
      (node (ref "VD1") (pin "P$1") (pinfunction "BLUE_P$1") (pintype "bidirectional"))
    )
    (net (code "46") (name "Net-(VD1-GREEN)") (class "Default")
      (node (ref "R2") (pin "2") (pinfunction "2_2") (pintype "passive"))
      (node (ref "VD1") (pin "P$2") (pinfunction "GREEN_P$2") (pintype "bidirectional"))
    )
    (net (code "47") (name "Net-(VD1-RED)") (class "Default")
      (node (ref "R1") (pin "2") (pinfunction "2_2") (pintype "passive"))
      (node (ref "VD1") (pin "P$4") (pinfunction "RED_P$4") (pintype "bidirectional"))
    )
    (net (code "48") (name "Net-(VD6-C)") (class "Default")
      (node (ref "R17") (pin "1") (pinfunction "1_1") (pintype "passive"))
      (node (ref "VD6") (pin "K") (pinfunction "C_K") (pintype "passive"))
    )
    (net (code "49") (name "Net-(VD7-C)") (class "Default")
      (node (ref "R18") (pin "1") (pinfunction "1_1") (pintype "passive"))
      (node (ref "VD7") (pin "K") (pinfunction "C_K") (pintype "passive"))
    )
    (net (code "50") (name "Net-(VD8-C)") (class "Default")
      (node (ref "R19") (pin "1") (pinfunction "1_1") (pintype "passive"))
      (node (ref "VD8") (pin "K") (pinfunction "C_K") (pintype "passive"))
    )
    (net (code "51") (name "Net-(VTL4-A)") (class "Default")
      (node (ref "R36") (pin "2") (pinfunction "2_2") (pintype "passive"))
      (node (ref "VTL4") (pin "1") (pinfunction "A_1") (pintype "passive"))
    )
    (net (code "52") (name "Net-(VTL4-COL)") (class "Default")
      (node (ref "R25") (pin "1") (pinfunction "1_1") (pintype "passive"))
      (node (ref "VT5") (pin "B") (pinfunction "B_B") (pintype "passive"))
      (node (ref "VTL4") (pin "4") (pinfunction "COL_4") (pintype "passive"))
    )
    (net (code "53") (name "Net-(VTL4-EMIT)") (class "Default")
      (node (ref "R34") (pin "2") (pinfunction "2_2") (pintype "passive"))
      (node (ref "VT5") (pin "C") (pinfunction "C_C") (pintype "passive"))
      (node (ref "VTL4") (pin "3") (pinfunction "EMIT_3") (pintype "passive"))
    )
    (net (code "54") (name "PB") (class "Default")
      (node (ref "C8") (pin "1") (pinfunction "1_1") (pintype "passive"))
      (node (ref "DA1") (pin "6") (pinfunction "VCC_6") (pintype "power_in"))
      (node (ref "R9") (pin "1") (pinfunction "1_1") (pintype "passive"))
      (node (ref "VD3") (pin "C") (pinfunction "C_C") (pintype "passive"))
      (node (ref "VD4") (pin "C") (pinfunction "C_C") (pintype "passive"))
      (node (ref "X3") (pin "3") (pinfunction "3_3") (pintype "passive"))
    )
    (net (code "55") (name "POW_CH") (class "Default")
      (node (ref "C2") (pin "1") (pinfunction "1_1") (pintype "passive"))
      (node (ref "R6") (pin "1") (pinfunction "1_1") (pintype "passive"))
      (node (ref "R7") (pin "2") (pinfunction "2_2") (pintype "passive"))
      (node (ref "VD2") (pin "A") (pinfunction "A_A") (pintype "passive"))
      (node (ref "X1") (pin "6") (pinfunction "6_6") (pintype "passive"))
    )
    (net (code "56") (name "READY") (class "Default")
      (node (ref "D1") (pin "7") (pinfunction "~{ST}_7") (pintype "input"))
      (node (ref "R19") (pin "2") (pinfunction "2_2") (pintype "passive"))
      (node (ref "SV1") (pin "2") (pinfunction "2_2") (pintype "passive"))
      (node (ref "SV2") (pin "3") (pinfunction "3_3") (pintype "passive"))
      (node (ref "X1") (pin "11") (pinfunction "11_11") (pintype "passive"))
      (node (ref "X6") (pin "8") (pinfunction "8_8") (pintype "passive"))
    )
    (net (code "57") (name "REPLY") (class "Default")
      (node (ref "SV2") (pin "2") (pinfunction "2_2") (pintype "passive"))
      (node (ref "X2") (pin "8") (pinfunction "8_8") (pintype "passive"))
      (node (ref "X7") (pin "11") (pinfunction "11_11") (pintype "passive"))
    )
    (net (code "58") (name "REQUEST") (class "Default")
      (node (ref "SV2") (pin "1") (pinfunction "1_1") (pintype "passive"))
      (node (ref "X2") (pin "9") (pinfunction "9_9") (pintype "passive"))
      (node (ref "X7") (pin "12") (pinfunction "12_12") (pintype "passive"))
    )
    (net (code "59") (name "RST") (class "Default")
      (node (ref "X2") (pin "7") (pinfunction "7_7") (pintype "passive"))
      (node (ref "X8") (pin "4") (pinfunction "4_4") (pintype "passive"))
    )
    (net (code "60") (name "RT") (class "Default")
      (node (ref "R4") (pin "2") (pinfunction "2_2") (pintype "passive"))
      (node (ref "R5") (pin "1") (pinfunction "1_1") (pintype "passive"))
      (node (ref "X3") (pin "9") (pinfunction "9_9") (pintype "passive"))
    )
    (net (code "61") (name "SD_CS") (class "Default")
      (node (ref "X2") (pin "17") (pinfunction "17_17") (pintype "passive"))
      (node (ref "X9") (pin "1") (pinfunction "1_1") (pintype "passive"))
    )
    (net (code "62") (name "SH++") (class "Default")
      (node (ref "C18") (pin "1") (pinfunction "1_1") (pintype "passive"))
      (node (ref "R23") (pin "1") (pinfunction "1_1") (pintype "passive"))
      (node (ref "X7") (pin "4") (pinfunction "4_4") (pintype "passive"))
    )
    (net (code "63") (name "SH-") (class "Default")
      (node (ref "R21") (pin "1") (pinfunction "1_1") (pintype "passive"))
      (node (ref "R22") (pin "2") (pinfunction "2_2") (pintype "passive"))
      (node (ref "VD11") (pin "C") (pinfunction "C_C") (pintype "passive"))
      (node (ref "VD12") (pin "A") (pinfunction "A_A") (pintype "passive"))
      (node (ref "X3") (pin "20") (pinfunction "20_20") (pintype "passive"))
    )
    (net (code "64") (name "SH--") (class "Default")
      (node (ref "C18") (pin "2") (pinfunction "2_2") (pintype "passive"))
      (node (ref "R22") (pin "1") (pinfunction "1_1") (pintype "passive"))
      (node (ref "X7") (pin "3") (pinfunction "3_3") (pintype "passive"))
    )
    (net (code "65") (name "TEST1") (class "Default")
      (node (ref "CH6") (pin "1") (pinfunction "P_1") (pintype "passive"))
      (node (ref "SV2") (pin "7") (pinfunction "7_7") (pintype "passive"))
    )
    (net (code "66") (name "TEST2") (class "Default")
      (node (ref "CH7") (pin "1") (pinfunction "P_1") (pintype "passive"))
      (node (ref "SV2") (pin "8") (pinfunction "8_8") (pintype "passive"))
    )
    (net (code "67") (name "TIRQ") (class "Default")
      (node (ref "X1") (pin "3") (pinfunction "3_3") (pintype "passive"))
      (node (ref "X8") (pin "14") (pinfunction "14_14") (pintype "passive"))
    )
    (net (code "68") (name "V5") (class "Default")
      (node (ref "C13") (pin "1") (pinfunction "1_1") (pintype "passive"))
      (node (ref "C17") (pin "1") (pinfunction "1_1") (pintype "passive"))
      (node (ref "R12") (pin "2") (pinfunction "2_2") (pintype "passive"))
      (node (ref "U3") (pin "4") (pinfunction "+VO_4") (pintype "power_in"))
      (node (ref "X6") (pin "1") (pinfunction "1_1") (pintype "passive"))
    )
    (net (code "69") (name "V_CLK") (class "Default")
      (node (ref "SV1") (pin "3") (pinfunction "3_3") (pintype "passive"))
      (node (ref "X2") (pin "11") (pinfunction "11_11") (pintype "passive"))
      (node (ref "X8") (pin "10") (pinfunction "10_10") (pintype "passive"))
      (node (ref "X8") (pin "7") (pinfunction "7_7") (pintype "passive"))
      (node (ref "X9") (pin "4") (pinfunction "4_4") (pintype "passive"))
    )
    (net (code "70") (name "V_MISO") (class "Default")
      (node (ref "SV1") (pin "4") (pinfunction "4_4") (pintype "passive"))
      (node (ref "X2") (pin "12") (pinfunction "12_12") (pintype "passive"))
      (node (ref "X8") (pin "13") (pinfunction "13_13") (pintype "passive"))
      (node (ref "X9") (pin "3") (pinfunction "3_3") (pintype "passive"))
    )
    (net (code "71") (name "V_MOSI") (class "Default")
      (node (ref "SV1") (pin "5") (pinfunction "5_5") (pintype "passive"))
      (node (ref "X2") (pin "18") (pinfunction "18_18") (pintype "passive"))
      (node (ref "X8") (pin "12") (pinfunction "12_12") (pintype "passive"))
      (node (ref "X8") (pin "6") (pinfunction "6_6") (pintype "passive"))
      (node (ref "X9") (pin "2") (pinfunction "2_2") (pintype "passive"))
    )
    (net (code "72") (name "V_SS") (class "Default")
      (node (ref "SV1") (pin "7") (pinfunction "7_7") (pintype "passive"))
      (node (ref "X2") (pin "10") (pinfunction "10_10") (pintype "passive"))
      (node (ref "X8") (pin "11") (pinfunction "11_11") (pintype "passive"))
    )
    (net (code "73") (name "unconnected-(D1-RST-Pad5)") (class "Default")
      (node (ref "D1") (pin "5") (pinfunction "RST_5") (pintype "output"))
    )
    (net (code "74") (name "unconnected-(D1-TOL-Pad3)") (class "Default")
      (node (ref "D1") (pin "3") (pinfunction "TOL_3") (pintype "input"))
    )
    (net (code "75") (name "unconnected-(D1-~{PBRST}-Pad1)") (class "Default")
      (node (ref "D1") (pin "1") (pinfunction "~{PBRST}_1") (pintype "input"))
    )
    (net (code "76") (name "unconnected-(J1-Pad2)") (class "Default")
      (node (ref "J1") (pin "2") (pinfunction "2_2") (pintype "passive"))
    )
    (net (code "77") (name "unconnected-(SV1-Pad9)") (class "Default")
      (node (ref "SV1") (pin "9") (pinfunction "9_9") (pintype "passive"))
    )
    (net (code "78") (name "unconnected-(SV2-Pad9)") (class "Default")
      (node (ref "SV2") (pin "9") (pinfunction "9_9") (pintype "passive"))
    )
    (net (code "79") (name "unconnected-(X1-Pad4)") (class "Default")
      (node (ref "X1") (pin "4") (pinfunction "4_4") (pintype "passive"))
    )
    (net (code "80") (name "unconnected-(X1-Pad13)") (class "Default")
      (node (ref "X1") (pin "13") (pinfunction "13_13") (pintype "passive"))
    )
    (net (code "81") (name "unconnected-(X1-Pad16)") (class "Default")
      (node (ref "X1") (pin "16") (pinfunction "16_16") (pintype "passive"))
    )
    (net (code "82") (name "unconnected-(X1-Pad17)") (class "Default")
      (node (ref "X1") (pin "17") (pinfunction "17_17") (pintype "passive"))
    )
    (net (code "83") (name "unconnected-(X1-Pad18)") (class "Default")
      (node (ref "X1") (pin "18") (pinfunction "18_18") (pintype "passive"))
    )
    (net (code "84") (name "unconnected-(X2-Pad1)") (class "Default")
      (node (ref "X2") (pin "1") (pinfunction "1_1") (pintype "passive"))
    )
    (net (code "85") (name "unconnected-(X2-Pad2)") (class "Default")
      (node (ref "X2") (pin "2") (pinfunction "2_2") (pintype "passive"))
    )
    (net (code "86") (name "unconnected-(X2-Pad3)") (class "Default")
      (node (ref "X2") (pin "3") (pinfunction "3_3") (pintype "passive"))
    )
    (net (code "87") (name "unconnected-(X2-Pad6)") (class "Default")
      (node (ref "X2") (pin "6") (pinfunction "6_6") (pintype "passive"))
    )
    (net (code "88") (name "unconnected-(X2-Pad15)") (class "Default")
      (node (ref "X2") (pin "15") (pinfunction "15_15") (pintype "passive"))
    )
    (net (code "89") (name "unconnected-(X2-Pad16)") (class "Default")
      (node (ref "X2") (pin "16") (pinfunction "16_16") (pintype "passive"))
    )
    (net (code "90") (name "unconnected-(X7-Pad1)") (class "Default")
      (node (ref "X7") (pin "1") (pinfunction "1_1") (pintype "passive"))
    )
    (net (code "91") (name "unconnected-(X7-Pad2)") (class "Default")
      (node (ref "X7") (pin "2") (pinfunction "2_2") (pintype "passive"))
    )
    (net (code "92") (name "unconnected-(X7-Pad5)") (class "Default")
      (node (ref "X7") (pin "5") (pinfunction "5_5") (pintype "passive"))
    )
    (net (code "93") (name "unconnected-(X7-Pad6)") (class "Default")
      (node (ref "X7") (pin "6") (pinfunction "6_6") (pintype "passive"))
    )
    (net (code "94") (name "unconnected-(X7-Pad7)") (class "Default")
      (node (ref "X7") (pin "7") (pinfunction "7_7") (pintype "passive"))
    )
    (net (code "95") (name "unconnected-(X7-Pad9)") (class "Default")
      (node (ref "X7") (pin "9") (pinfunction "9_9") (pintype "passive"))
    )
    (net (code "96") (name "unconnected-(X7-Pad10)") (class "Default")
      (node (ref "X7") (pin "10") (pinfunction "10_10") (pintype "passive"))
    )
    (net (code "97") (name "unconnected-(X8-Pad9)") (class "Default")
      (node (ref "X8") (pin "9") (pinfunction "9_9") (pintype "passive"))
    )
    (net (code "98") (name "{slash}OUT") (class "Default")
      (node (ref "SV2") (pin "6") (pinfunction "6_6") (pintype "passive"))
      (node (ref "X3") (pin "10") (pinfunction "10_10") (pintype "passive"))
      (node (ref "X6") (pin "13") (pinfunction "13_13") (pintype "passive"))
    )
    (net (code "99") (name "{slash}SW") (class "Default")
      (node (ref "SV2") (pin "5") (pinfunction "5_5") (pintype "passive"))
      (node (ref "VTL4") (pin "2") (pinfunction "C_2") (pintype "passive"))
      (node (ref "X6") (pin "5") (pinfunction "5_5") (pintype "passive"))
    )
  )
)
